# PCIE_CON.net
KiCad netlist of a schematic drawn in Altium Designer
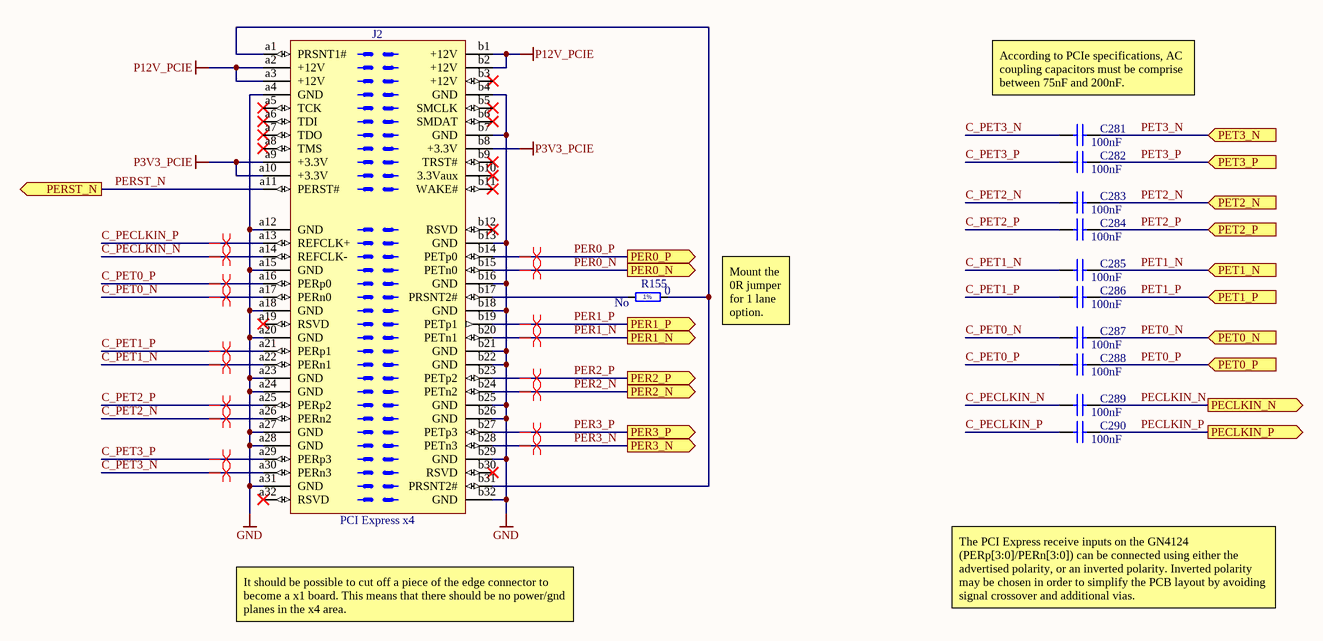
[diagram p0: PCIE_CON.SchDoc]

(export (version "E")
  (design (tool "Eeschema 10.0.6"))
  (components
    (comp (ref "C281")
      (value "100nF")
      (footprint "CAPC1005X55N")
      (description "Non-polarised capacitor")
      (fields
        (field (name "PART NUMBER") "CC0402_100NF_16V_10%_X7R")
        (field (name "VOLTAGE") "16V")
        (field (name "AUTHOR") "CERN DEM JLC")
      )
      (libsource (lib "Capacitors") (part "Capacitor - non polarized"))
    )
    (comp (ref "C282")
      (value "100nF")
      (footprint "CAPC1005X55N")
      (description "Non-polarised capacitor")
      (fields
        (field (name "PART NUMBER") "CC0402_100NF_16V_10%_X7R")
        (field (name "VOLTAGE") "16V")
        (field (name "AUTHOR") "CERN DEM JLC")
      )
      (libsource (lib "Capacitors") (part "Capacitor - non polarized"))
    )
    (comp (ref "C283")
      (value "100nF")
      (footprint "CAPC1005X55N")
      (description "Non-polarised capacitor")
      (fields
        (field (name "PART NUMBER") "CC0402_100NF_16V_10%_X7R")
        (field (name "VOLTAGE") "16V")
        (field (name "AUTHOR") "CERN DEM JLC")
      )
      (libsource (lib "Capacitors") (part "Capacitor - non polarized"))
    )
    (comp (ref "C284")
      (value "100nF")
      (footprint "CAPC1005X55N")
      (description "Non-polarised capacitor")
      (fields
        (field (name "PART NUMBER") "CC0402_100NF_16V_10%_X7R")
        (field (name "VOLTAGE") "16V")
        (field (name "AUTHOR") "CERN DEM JLC")
      )
      (libsource (lib "Capacitors") (part "Capacitor - non polarized"))
    )
    (comp (ref "C285")
      (value "100nF")
      (footprint "CAPC1005X55N")
      (description "Non-polarised capacitor")
      (fields
        (field (name "PART NUMBER") "CC0402_100NF_16V_10%_X7R")
        (field (name "VOLTAGE") "16V")
        (field (name "AUTHOR") "CERN DEM JLC")
      )
      (libsource (lib "Capacitors") (part "Capacitor - non polarized"))
    )
    (comp (ref "C286")
      (value "100nF")
      (footprint "CAPC1005X55N")
      (description "Non-polarised capacitor")
      (fields
        (field (name "PART NUMBER") "CC0402_100NF_16V_10%_X7R")
        (field (name "VOLTAGE") "16V")
        (field (name "AUTHOR") "CERN DEM JLC")
      )
      (libsource (lib "Capacitors") (part "Capacitor - non polarized"))
    )
    (comp (ref "C287")
      (value "100nF")
      (footprint "CAPC1005X55N")
      (description "Non-polarised capacitor")
      (fields
        (field (name "PART NUMBER") "CC0402_100NF_16V_10%_X7R")
        (field (name "VOLTAGE") "16V")
        (field (name "AUTHOR") "CERN DEM JLC")
      )
      (libsource (lib "Capacitors") (part "Capacitor - non polarized"))
    )
    (comp (ref "C288")
      (value "100nF")
      (footprint "CAPC1005X55N")
      (description "Non-polarised capacitor")
      (fields
        (field (name "PART NUMBER") "CC0402_100NF_16V_10%_X7R")
        (field (name "VOLTAGE") "16V")
        (field (name "AUTHOR") "CERN DEM JLC")
      )
      (libsource (lib "Capacitors") (part "Capacitor - non polarized"))
    )
    (comp (ref "C289")
      (value "100nF")
      (footprint "CAPC1005X55N")
      (description "Non-polarised capacitor")
      (fields
        (field (name "PART NUMBER") "CC0402_100NF_16V_10%_X7R")
        (field (name "VOLTAGE") "16V")
        (field (name "AUTHOR") "CERN DEM JLC")
      )
      (libsource (lib "Capacitors") (part "Capacitor - non polarized"))
    )
    (comp (ref "C290")
      (value "100nF")
      (footprint "CAPC1005X55N")
      (description "Non-polarised capacitor")
      (fields
        (field (name "PART NUMBER") "CC0402_100NF_16V_10%_X7R")
        (field (name "VOLTAGE") "16V")
        (field (name "AUTHOR") "CERN DEM JLC")
      )
      (libsource (lib "Capacitors") (part "Capacitor - non polarized"))
    )
    (comp (ref "J2")
      (value "PCI Express x4")
      (footprint "PCI Express x4")
      (description "64 contacts Board Eddge PCI Express x4 Connector")
      (fields (field (name "MANUFACTURER") "PCI-SIG") (field (name "AUTHOR") "CERN DEM JLC"))
      (libsource (lib "Connectors") (part "PCI Express x4"))
    )
    (comp (ref "R155")
      (value "0")
      (footprint "RESC1608X55N")
      (description "Resistor - 1%")
      (fields
        (field (name "PART NUMBER") "R0603_0R_JUMPER")
        (field (name "MANUFACTURER") "GENERIC")
        (field (name "MOUNTED") "No")
        (field (name "AUTHOR") "CERN DEM JLC")
      )
      (libsource (lib "Resistors") (part "Resistor - 1%"))
    )
  )
  (nets
    (net (code "1") (name "/C_PECLKIN_N") (class "Default")
      (node (ref "C289") (pin "1") (pinfunction "1_1") (pintype "passive"))
      (node (ref "J2") (pin "a14") (pinfunction "REFCLK-_a14") (pintype "bidirectional"))
    )
    (net (code "2") (name "/C_PECLKIN_P") (class "Default")
      (node (ref "C290") (pin "1") (pinfunction "1_1") (pintype "passive"))
      (node (ref "J2") (pin "a13") (pinfunction "REFCLK+_a13") (pintype "bidirectional"))
    )
    (net (code "3") (name "/C_PET0_N") (class "Default")
      (node (ref "C287") (pin "1") (pinfunction "1_1") (pintype "passive"))
      (node (ref "J2") (pin "a17") (pinfunction "PERn0_a17") (pintype "bidirectional"))
    )
    (net (code "4") (name "/C_PET0_P") (class "Default")
      (node (ref "C288") (pin "1") (pinfunction "1_1") (pintype "passive"))
      (node (ref "J2") (pin "a16") (pinfunction "PERp0_a16") (pintype "bidirectional"))
    )
    (net (code "5") (name "/C_PET1_N") (class "Default")
      (node (ref "C285") (pin "1") (pinfunction "1_1") (pintype "passive"))
      (node (ref "J2") (pin "a22") (pinfunction "PERn1_a22") (pintype "bidirectional"))
    )
    (net (code "6") (name "/C_PET1_P") (class "Default")
      (node (ref "C286") (pin "1") (pinfunction "1_1") (pintype "passive"))
      (node (ref "J2") (pin "a21") (pinfunction "PERp1_a21") (pintype "bidirectional"))
    )
    (net (code "7") (name "/C_PET2_N") (class "Default")
      (node (ref "C283") (pin "1") (pinfunction "1_1") (pintype "passive"))
      (node (ref "J2") (pin "a26") (pinfunction "PERn2_a26") (pintype "bidirectional"))
    )
    (net (code "8") (name "/C_PET2_P") (class "Default")
      (node (ref "C284") (pin "1") (pinfunction "1_1") (pintype "passive"))
      (node (ref "J2") (pin "a25") (pinfunction "PERp2_a25") (pintype "bidirectional"))
    )
    (net (code "9") (name "/C_PET3_N") (class "Default")
      (node (ref "C281") (pin "1") (pinfunction "1_1") (pintype "passive"))
      (node (ref "J2") (pin "a30") (pinfunction "PERn3_a30") (pintype "bidirectional"))
    )
    (net (code "10") (name "/C_PET3_P") (class "Default")
      (node (ref "C282") (pin "1") (pinfunction "1_1") (pintype "passive"))
      (node (ref "J2") (pin "a29") (pinfunction "PERp3_a29") (pintype "bidirectional"))
    )
    (net (code "11") (name "/PECLKIN_N") (class "Default")
      (node (ref "C289") (pin "2") (pinfunction "2_2") (pintype "passive"))
    )
    (net (code "12") (name "/PECLKIN_P") (class "Default")
      (node (ref "C290") (pin "2") (pinfunction "2_2") (pintype "passive"))
    )
    (net (code "13") (name "/PER0_N") (class "Default")
      (node (ref "J2") (pin "b15") (pinfunction "PETn0_b15") (pintype "bidirectional"))
    )
    (net (code "14") (name "/PER0_P") (class "Default")
      (node (ref "J2") (pin "b14") (pinfunction "PETp0_b14") (pintype "bidirectional"))
    )
    (net (code "15") (name "/PER1_N") (class "Default")
      (node (ref "J2") (pin "b20") (pinfunction "PETn1_b20") (pintype "bidirectional"))
    )
    (net (code "16") (name "/PER1_P") (class "Default")
      (node (ref "J2") (pin "b19") (pinfunction "PETp1_b19") (pintype "output"))
    )
    (net (code "17") (name "/PER2_N") (class "Default")
      (node (ref "J2") (pin "b24") (pinfunction "PETn2_b24") (pintype "bidirectional"))
    )
    (net (code "18") (name "/PER2_P") (class "Default")
      (node (ref "J2") (pin "b23") (pinfunction "PETp2_b23") (pintype "bidirectional"))
    )
    (net (code "19") (name "/PER3_N") (class "Default")
      (node (ref "J2") (pin "b28") (pinfunction "PETn3_b28") (pintype "bidirectional"))
    )
    (net (code "20") (name "/PER3_P") (class "Default")
      (node (ref "J2") (pin "b27") (pinfunction "PETp3_b27") (pintype "bidirectional"))
    )
    (net (code "21") (name "/PERST_N") (class "Default")
      (node (ref "J2") (pin "a11") (pinfunction "PERST#_a11") (pintype "bidirectional"))
    )
    (net (code "22") (name "/PET0_N") (class "Default")
      (node (ref "C287") (pin "2") (pinfunction "2_2") (pintype "passive"))
    )
    (net (code "23") (name "/PET0_P") (class "Default")
      (node (ref "C288") (pin "2") (pinfunction "2_2") (pintype "passive"))
    )
    (net (code "24") (name "/PET1_N") (class "Default")
      (node (ref "C285") (pin "2") (pinfunction "2_2") (pintype "passive"))
    )
    (net (code "25") (name "/PET1_P") (class "Default")
      (node (ref "C286") (pin "2") (pinfunction "2_2") (pintype "passive"))
    )
    (net (code "26") (name "/PET2_N") (class "Default")
      (node (ref "C283") (pin "2") (pinfunction "2_2") (pintype "passive"))
    )
    (net (code "27") (name "/PET2_P") (class "Default")
      (node (ref "C284") (pin "2") (pinfunction "2_2") (pintype "passive"))
    )
    (net (code "28") (name "/PET3_N") (class "Default")
      (node (ref "C281") (pin "2") (pinfunction "2_2") (pintype "passive"))
    )
    (net (code "29") (name "/PET3_P") (class "Default")
      (node (ref "C282") (pin "2") (pinfunction "2_2") (pintype "passive"))
    )
    (net (code "30") (name "GND") (class "Default")
      (node (ref "J2") (pin "a12") (pinfunction "GND_a12") (pintype "power_in"))
      (node (ref "J2") (pin "a15") (pinfunction "GND_a15") (pintype "power_in"))
      (node (ref "J2") (pin "a18") (pinfunction "GND_a18") (pintype "power_in"))
      (node (ref "J2") (pin "a20") (pinfunction "GND_a20") (pintype "power_in"))
      (node (ref "J2") (pin "a23") (pinfunction "GND_a23") (pintype "power_in"))
      (node (ref "J2") (pin "a24") (pinfunction "GND_a24") (pintype "power_in"))
      (node (ref "J2") (pin "a27") (pinfunction "GND_a27") (pintype "power_in"))
      (node (ref "J2") (pin "a28") (pinfunction "GND_a28") (pintype "power_in"))
      (node (ref "J2") (pin "a31") (pinfunction "GND_a31") (pintype "power_in"))
      (node (ref "J2") (pin "a4") (pinfunction "GND_a4") (pintype "power_in"))
      (node (ref "J2") (pin "b13") (pinfunction "GND_b13") (pintype "power_in"))
      (node (ref "J2") (pin "b16") (pinfunction "GND_b16") (pintype "power_in"))
      (node (ref "J2") (pin "b18") (pinfunction "GND_b18") (pintype "power_in"))
      (node (ref "J2") (pin "b21") (pinfunction "GND_b21") (pintype "power_in"))
      (node (ref "J2") (pin "b22") (pinfunction "GND_b22") (pintype "power_in"))
      (node (ref "J2") (pin "b25") (pinfunction "GND_b25") (pintype "power_in"))
      (node (ref "J2") (pin "b26") (pinfunction "GND_b26") (pintype "power_in"))
      (node (ref "J2") (pin "b29") (pinfunction "GND_b29") (pintype "power_in"))
      (node (ref "J2") (pin "b32") (pinfunction "GND_b32") (pintype "power_in"))
      (node (ref "J2") (pin "b4") (pinfunction "GND_b4") (pintype "power_in"))
      (node (ref "J2") (pin "b7") (pinfunction "GND_b7") (pintype "power_in"))
    )
    (net (code "31") (name "Net-(J2-PRSNT1#)") (class "Default")
      (node (ref "J2") (pin "a1") (pinfunction "PRSNT1#_a1") (pintype "bidirectional"))
      (node (ref "J2") (pin "b31") (pinfunction "PRSNT2#_b31") (pintype "bidirectional"))
      (node (ref "R155") (pin "2") (pinfunction "2_2") (pintype "passive"))
    )
    (net (code "32") (name "Net-(J2-PRSNT2#-Padb17)") (class "Default")
      (node (ref "J2") (pin "b17") (pinfunction "PRSNT2#_b17") (pintype "bidirectional"))
      (node (ref "R155") (pin "1") (pinfunction "1_1") (pintype "passive"))
    )
    (net (code "33") (name "P3V3_PCIE") (class "Default")
      (node (ref "J2") (pin "a10") (pinfunction "+3.3V_a10") (pintype "power_in"))
      (node (ref "J2") (pin "a9") (pinfunction "+3.3V_a9") (pintype "power_in"))
      (node (ref "J2") (pin "b8") (pinfunction "+3.3V_b8") (pintype "power_in"))
    )
    (net (code "34") (name "P12V_PCIE") (class "Default")
      (node (ref "J2") (pin "a2") (pinfunction "+12V_a2") (pintype "power_in"))
      (node (ref "J2") (pin "a3") (pinfunction "+12V_a3") (pintype "power_in"))
      (node (ref "J2") (pin "b1") (pinfunction "+12V_b1") (pintype "power_in"))
      (node (ref "J2") (pin "b2") (pinfunction "+12V_b2") (pintype "power_in"))
    )
    (net (code "35") (name "unconnected-(J2-+12V-Padb3)") (class "Default")
      (node (ref "J2") (pin "b3") (pinfunction "+12V_b3") (pintype "bidirectional+no_connect"))
    )
    (net (code "36") (name "unconnected-(J2-3.3Vaux-Padb10)") (class "Default")
      (node (ref "J2") (pin "b10") (pinfunction "3.3Vaux_b10") (pintype "power_in+no_connect"))
    )
    (net (code "37") (name "unconnected-(J2-RSVD-Pada19)") (class "Default")
      (node (ref "J2") (pin "a19") (pinfunction "RSVD_a19") (pintype "bidirectional+no_connect"))
    )
    (net (code "38") (name "unconnected-(J2-RSVD-Pada32)") (class "Default")
      (node (ref "J2") (pin "a32") (pinfunction "RSVD_a32") (pintype "bidirectional+no_connect"))
    )
    (net (code "39") (name "unconnected-(J2-RSVD-Padb12)") (class "Default")
      (node (ref "J2") (pin "b12") (pinfunction "RSVD_b12") (pintype "bidirectional+no_connect"))
    )
    (net (code "40") (name "unconnected-(J2-RSVD-Padb30)") (class "Default")
      (node (ref "J2") (pin "b30") (pinfunction "RSVD_b30") (pintype "bidirectional+no_connect"))
    )
    (net (code "41") (name "unconnected-(J2-SMCLK-Padb5)") (class "Default")
      (node (ref "J2") (pin "b5") (pinfunction "SMCLK_b5") (pintype "bidirectional+no_connect"))
    )
    (net (code "42") (name "unconnected-(J2-SMDAT-Padb6)") (class "Default")
      (node (ref "J2") (pin "b6") (pinfunction "SMDAT_b6") (pintype "bidirectional+no_connect"))
    )
    (net (code "43") (name "unconnected-(J2-TCK-Pada5)") (class "Default")
      (node (ref "J2") (pin "a5") (pinfunction "TCK_a5") (pintype "bidirectional+no_connect"))
    )
    (net (code "44") (name "unconnected-(J2-TDI-Pada6)") (class "Default")
      (node (ref "J2") (pin "a6") (pinfunction "TDI_a6") (pintype "bidirectional+no_connect"))
    )
    (net (code "45") (name "unconnected-(J2-TDO-Pada7)") (class "Default")
      (node (ref "J2") (pin "a7") (pinfunction "TDO_a7") (pintype "bidirectional+no_connect"))
    )
    (net (code "46") (name "unconnected-(J2-TMS-Pada8)") (class "Default")
      (node (ref "J2") (pin "a8") (pinfunction "TMS_a8") (pintype "bidirectional+no_connect"))
    )
    (net (code "47") (name "unconnected-(J2-TRST#-Padb9)") (class "Default")
      (node (ref "J2") (pin "b9") (pinfunction "TRST#_b9") (pintype "bidirectional+no_connect"))
    )
    (net (code "48") (name "unconnected-(J2-WAKE#-Padb11)") (class "Default")
      (node (ref "J2") (pin "b11") (pinfunction "WAKE#_b11") (pintype "bidirectional+no_connect"))
    )
  )
)
